# Overvoltage_Protection.net
KiCad netlist of a schematic drawn in EAGLE
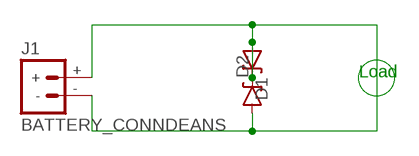
[diagram p0: schematic, sheet 1]

(export (version "E")
  (design (tool "Eeschema 10.0.6"))
  (components
    (comp (ref "D1")
      (value "DIODE-ZENERPTH")
      (footprint "eagle-import:DIODE-ZENER")
      (libsource (lib "eagle-import") (part "DIODE-ZENERPTH"))
    )
    (comp (ref "D2")
      (value "DIODE-ZENERPTH")
      (footprint "eagle-import:DIODE-ZENER")
      (libsource (lib "eagle-import") (part "DIODE-ZENERPTH"))
    )
    (comp (ref "J1")
      (value "BATTERY_CONNDEANS")
      (footprint "eagle-import:DEANS")
      (libsource (lib "eagle-import") (part "BATTERY_CONNDEANS"))
    )
  )
  (nets
    (net (code "1") (name "Net-(D1-A)") (class "Default")
      (node (ref "D1") (pin "P$1") (pinfunction "C_P$1") (pintype "passive"))
      (node (ref "D1") (pin "P$2") (pinfunction "A_P$2") (pintype "passive"))
      (node (ref "D2") (pin "P$1") (pinfunction "C_P$1") (pintype "passive"))
      (node (ref "D2") (pin "P$2") (pinfunction "A_P$2") (pintype "passive"))
      (node (ref "J1") (pin "+") (pinfunction "+_+") (pintype "passive"))
      (node (ref "J1") (pin "-") (pinfunction "-_-") (pintype "passive"))
    )
  )
)
